# OneInchRound.net
KiCad netlist of a schematic drawn in EAGLE
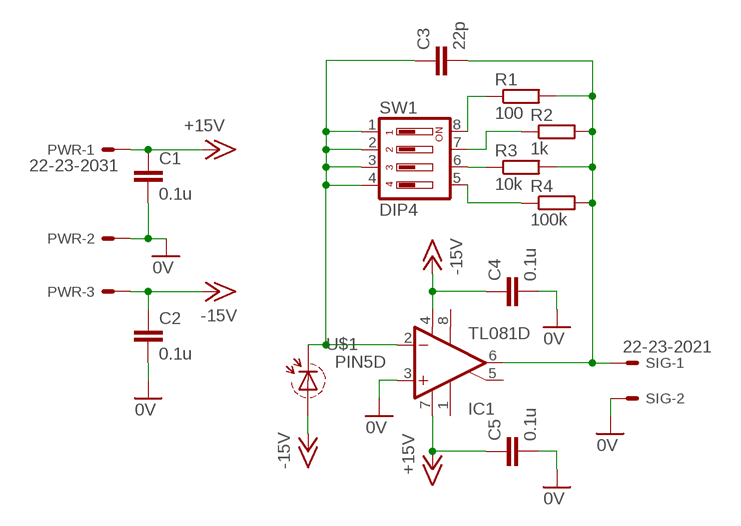
[diagram p0: schematic, sheet 1]

(export (version "E")
  (design (tool "Eeschema 10.0.6"))
  (components
    (comp (ref "C1")
      (value "0.1u")
      (footprint "eagle-import:C0805")
      (libsource (lib "eagle-import") (part "C-EUC0805"))
    )
    (comp (ref "C2")
      (value "0.1u")
      (footprint "eagle-import:C0805")
      (libsource (lib "eagle-import") (part "C-EUC0805"))
    )
    (comp (ref "C3")
      (value "22p")
      (footprint "eagle-import:C0805")
      (libsource (lib "eagle-import") (part "C-EUC0805"))
    )
    (comp (ref "C4")
      (value "0.1u")
      (footprint "eagle-import:C0805")
      (libsource (lib "eagle-import") (part "C-EUC0805"))
    )
    (comp (ref "C5")
      (value "0.1u")
      (footprint "eagle-import:C0805")
      (libsource (lib "eagle-import") (part "C-EUC0805"))
    )
    (comp (ref "IC1")
      (value "TL081D")
      (footprint "eagle-import:SO08")
      (libsource (lib "eagle-import") (part "TL081D"))
    )
    (comp (ref "PWR")
      (value "22-23-2031")
      (footprint "eagle-import:22-23-2031")
      (fields (field (name "MF") "MOLEX"))
      (libsource (lib "eagle-import") (part "22-23-2031"))
    )
    (comp (ref "R1")
      (value "100")
      (footprint "eagle-import:R0805")
      (libsource (lib "eagle-import") (part "R-EU_R0805"))
    )
    (comp (ref "R2")
      (value "1k")
      (footprint "eagle-import:R0805")
      (libsource (lib "eagle-import") (part "R-EU_R0805"))
    )
    (comp (ref "R3")
      (value "10k")
      (footprint "eagle-import:R0805")
      (libsource (lib "eagle-import") (part "R-EU_R0805"))
    )
    (comp (ref "R4")
      (value "100k")
      (footprint "eagle-import:R0805")
      (libsource (lib "eagle-import") (part "R-EU_R0805"))
    )
    (comp (ref "SIG")
      (value "22-23-2021")
      (footprint "eagle-import:22-23-2021")
      (fields (field (name "MF") "MOLEX"))
      (libsource (lib "eagle-import") (part "22-23-2021"))
    )
    (comp (ref "SW1")
      (value "DIP4")
      (footprint "eagle-import:SO08")
      (libsource (lib "eagle-import") (part "DIP4"))
    )
    (comp (ref "U$1")
      (value "PIN5D")
      (footprint "eagle-import:TO5_2P")
      (libsource (lib "eagle-import") (part "PIN5D"))
    )
  )
  (nets
    (net (code "1") (name "+15V") (class "Default")
      (node (ref "C1") (pin "1") (pinfunction "1_1") (pintype "passive"))
      (node (ref "C5") (pin "1") (pinfunction "1_1") (pintype "passive"))
      (node (ref "IC1") (pin "7") (pinfunction "V+_7") (pintype "power_in"))
      (node (ref "PWR") (pin "1") (pinfunction "S_1") (pintype "passive"))
    )
    (net (code "2") (name "-15V") (class "Default")
      (node (ref "C2") (pin "1") (pinfunction "1_1") (pintype "passive"))
      (node (ref "C4") (pin "1") (pinfunction "1_1") (pintype "passive"))
      (node (ref "IC1") (pin "4") (pinfunction "V-_4") (pintype "power_in"))
      (node (ref "PWR") (pin "3") (pinfunction "S_3") (pintype "passive"))
      (node (ref "U$1") (pin "1") (pinfunction "ANODE_1") (pintype "passive"))
    )
    (net (code "3") (name "0V") (class "Default")
      (node (ref "C1") (pin "2") (pinfunction "2_2") (pintype "passive"))
      (node (ref "C2") (pin "2") (pinfunction "2_2") (pintype "passive"))
      (node (ref "C4") (pin "2") (pinfunction "2_2") (pintype "passive"))
      (node (ref "C5") (pin "2") (pinfunction "2_2") (pintype "passive"))
      (node (ref "IC1") (pin "3") (pinfunction "+IN_3") (pintype "input"))
      (node (ref "PWR") (pin "2") (pinfunction "S_2") (pintype "passive"))
      (node (ref "SIG") (pin "2") (pinfunction "S_2") (pintype "passive"))
    )
    (net (code "4") (name "Net-(IC1--IN)") (class "Default")
      (node (ref "C3") (pin "1") (pinfunction "1_1") (pintype "passive"))
      (node (ref "IC1") (pin "2") (pinfunction "-IN_2") (pintype "input"))
      (node (ref "SW1") (pin "1") (pinfunction "1_1") (pintype "passive"))
      (node (ref "SW1") (pin "2") (pinfunction "2_2") (pintype "passive"))
      (node (ref "SW1") (pin "3") (pinfunction "3_3") (pintype "passive"))
      (node (ref "SW1") (pin "4") (pinfunction "4_4") (pintype "passive"))
      (node (ref "U$1") (pin "3") (pinfunction "CATH_3") (pintype "passive"))
    )
    (net (code "5") (name "Net-(IC1-OUT)") (class "Default")
      (node (ref "C3") (pin "2") (pinfunction "2_2") (pintype "passive"))
      (node (ref "IC1") (pin "6") (pinfunction "OUT_6") (pintype "output"))
      (node (ref "R1") (pin "2") (pinfunction "2_2") (pintype "passive"))
      (node (ref "R2") (pin "2") (pinfunction "2_2") (pintype "passive"))
      (node (ref "R3") (pin "2") (pinfunction "2_2") (pintype "passive"))
      (node (ref "R4") (pin "2") (pinfunction "2_2") (pintype "passive"))
      (node (ref "SIG") (pin "1") (pinfunction "S_1") (pintype "passive"))
    )
    (net (code "6") (name "Net-(R1-Pad1)") (class "Default")
      (node (ref "R1") (pin "1") (pinfunction "1_1") (pintype "passive"))
      (node (ref "SW1") (pin "8") (pinfunction "8_8") (pintype "passive"))
    )
    (net (code "7") (name "Net-(R2-Pad1)") (class "Default")
      (node (ref "R2") (pin "1") (pinfunction "1_1") (pintype "passive"))
      (node (ref "SW1") (pin "7") (pinfunction "7_7") (pintype "passive"))
    )
    (net (code "8") (name "Net-(R3-Pad1)") (class "Default")
      (node (ref "R3") (pin "1") (pinfunction "1_1") (pintype "passive"))
      (node (ref "SW1") (pin "6") (pinfunction "6_6") (pintype "passive"))
    )
    (net (code "9") (name "Net-(R4-Pad1)") (class "Default")
      (node (ref "R4") (pin "1") (pinfunction "1_1") (pintype "passive"))
      (node (ref "SW1") (pin "5") (pinfunction "5_5") (pintype "passive"))
    )
    (net (code "10") (name "unconnected-(IC1-ON1-Pad1)") (class "Default")
      (node (ref "IC1") (pin "1") (pinfunction "ON1_1") (pintype "passive"))
    )
    (net (code "11") (name "unconnected-(IC1-ON2-Pad5)") (class "Default")
      (node (ref "IC1") (pin "5") (pinfunction "ON2_5") (pintype "passive"))
    )
    (net (code "12") (name "unconnected-(IC1-OPT-Pad8)") (class "Default")
      (node (ref "IC1") (pin "8") (pinfunction "OPT_8") (pintype "passive"))
    )
  )
)
